# Sheet_1_2023-04-12.net
KiCad netlist of a schematic drawn in Altium Designer
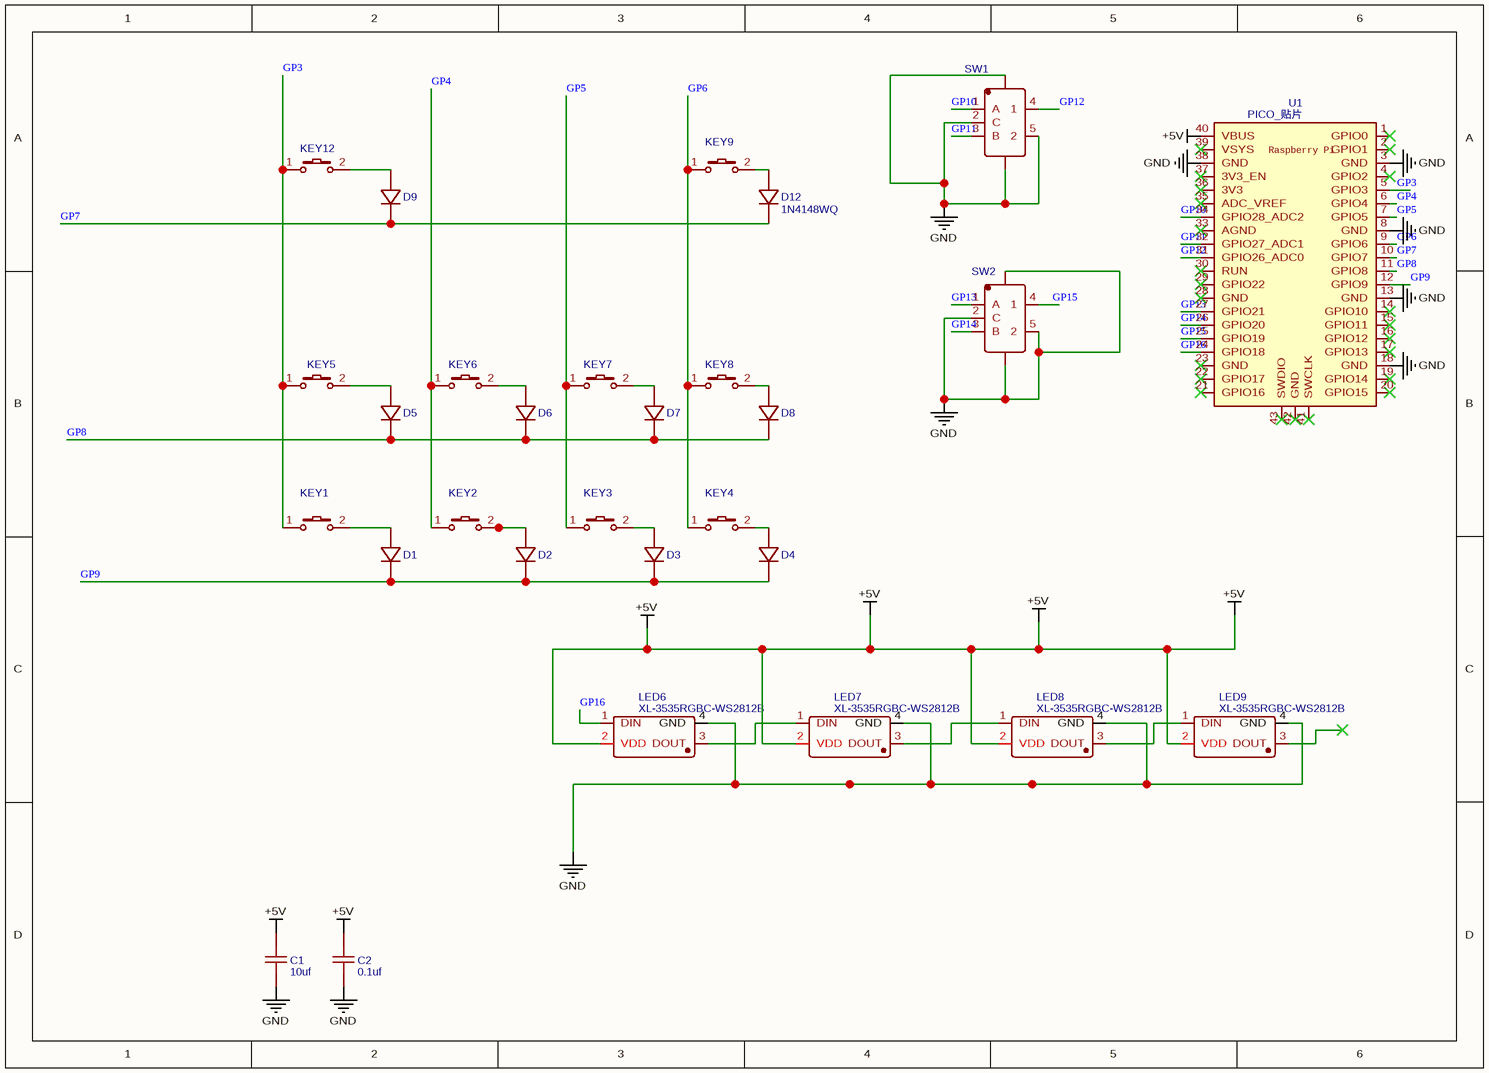
[diagram p0: Sheet_1_2023-04-12.schdoc]

(export (version "E")
  (design (tool "Eeschema 10.0.6"))
  (components
    (comp (ref "C1")
      (value "10uf")
      (fields (field (name "CONTRIBUTOR") "LCEDA_Lib"))
      (libsource (lib "altium-import") (part "root_1_10uf_"))
    )
    (comp (ref "C2")
      (value "0.1uf")
      (fields (field (name "CONTRIBUTOR") "LCEDA_Lib"))
      (libsource (lib "altium-import") (part "root_1_0.1uf_"))
    )
    (comp (ref "D1")
      (value "1N4148WQ")
      (fields (field (name "BOM_SUPPLIER PART") "C2942441") (field (name "CONTRIBUTOR") "lcsc"))
      (libsource (lib "altium-import") (part "root_1_1N4148WQ_"))
    )
    (comp (ref "D2")
      (value "1N4148WQ")
      (fields (field (name "BOM_SUPPLIER PART") "C2942441") (field (name "CONTRIBUTOR") "lcsc"))
      (libsource (lib "altium-import") (part "root_1_1N4148WQ_"))
    )
    (comp (ref "D3")
      (value "1N4148WQ")
      (fields (field (name "BOM_SUPPLIER PART") "C2942441") (field (name "CONTRIBUTOR") "lcsc"))
      (libsource (lib "altium-import") (part "root_1_1N4148WQ_"))
    )
    (comp (ref "D4")
      (value "1N4148WQ")
      (fields (field (name "BOM_SUPPLIER PART") "C2942441") (field (name "CONTRIBUTOR") "lcsc"))
      (libsource (lib "altium-import") (part "root_1_1N4148WQ_"))
    )
    (comp (ref "D5")
      (value "1N4148WQ")
      (fields (field (name "BOM_SUPPLIER PART") "C2942441") (field (name "CONTRIBUTOR") "lcsc"))
      (libsource (lib "altium-import") (part "root_1_1N4148WQ_"))
    )
    (comp (ref "D6")
      (value "1N4148WQ")
      (fields (field (name "BOM_SUPPLIER PART") "C2942441") (field (name "CONTRIBUTOR") "lcsc"))
      (libsource (lib "altium-import") (part "root_1_1N4148WQ_"))
    )
    (comp (ref "D7")
      (value "1N4148WQ")
      (fields (field (name "BOM_SUPPLIER PART") "C2942441") (field (name "CONTRIBUTOR") "lcsc"))
      (libsource (lib "altium-import") (part "root_1_1N4148WQ_"))
    )
    (comp (ref "D8")
      (value "1N4148WQ")
      (fields (field (name "BOM_SUPPLIER PART") "C2942441") (field (name "CONTRIBUTOR") "lcsc"))
      (libsource (lib "altium-import") (part "root_1_1N4148WQ_"))
    )
    (comp (ref "D9")
      (value "1N4148WQ")
      (fields (field (name "BOM_SUPPLIER PART") "C2942441") (field (name "CONTRIBUTOR") "lcsc"))
      (libsource (lib "altium-import") (part "root_1_1N4148WQ_"))
    )
    (comp (ref "D12")
      (value "1N4148WQ")
      (fields (field (name "BOM_SUPPLIER PART") "C2942441") (field (name "CONTRIBUTOR") "lcsc"))
      (libsource (lib "altium-import") (part "root_1_1N4148WQ_"))
    )
    (comp (ref "KEY1")
      (value "K2-3.6×6.1_SMD")
      (fields
        (field (name "BOM_SUPPLIER PART") "C118141")
        (field (name "BOM_MANUFACTURER PART") "K2-1107ST-A4SW-06")
        (field (name "CONTRIBUTOR") "LCEDA_Lib")
      )
      (libsource (lib "altium-import") (part "root_0_K2-3.6×6.1_SMD_"))
    )
    (comp (ref "KEY2")
      (value "K2-3.6×6.1_SMD")
      (fields
        (field (name "BOM_SUPPLIER PART") "C118141")
        (field (name "BOM_MANUFACTURER PART") "K2-1107ST-A4SW-06")
        (field (name "CONTRIBUTOR") "LCEDA_Lib")
      )
      (libsource (lib "altium-import") (part "root_0_K2-3.6×6.1_SMD_"))
    )
    (comp (ref "KEY3")
      (value "K2-3.6×6.1_SMD")
      (fields
        (field (name "BOM_SUPPLIER PART") "C118141")
        (field (name "BOM_MANUFACTURER PART") "K2-1107ST-A4SW-06")
        (field (name "CONTRIBUTOR") "LCEDA_Lib")
      )
      (libsource (lib "altium-import") (part "root_0_K2-3.6×6.1_SMD_"))
    )
    (comp (ref "KEY4")
      (value "K2-3.6×6.1_SMD")
      (fields
        (field (name "BOM_SUPPLIER PART") "C118141")
        (field (name "BOM_MANUFACTURER PART") "K2-1107ST-A4SW-06")
        (field (name "CONTRIBUTOR") "LCEDA_Lib")
      )
      (libsource (lib "altium-import") (part "root_0_K2-3.6×6.1_SMD_"))
    )
    (comp (ref "KEY5")
      (value "K2-3.6×6.1_SMD")
      (fields
        (field (name "BOM_SUPPLIER PART") "C118141")
        (field (name "BOM_MANUFACTURER PART") "K2-1107ST-A4SW-06")
        (field (name "CONTRIBUTOR") "LCEDA_Lib")
      )
      (libsource (lib "altium-import") (part "root_0_K2-3.6×6.1_SMD_"))
    )
    (comp (ref "KEY6")
      (value "K2-3.6×6.1_SMD")
      (fields
        (field (name "BOM_SUPPLIER PART") "C118141")
        (field (name "BOM_MANUFACTURER PART") "K2-1107ST-A4SW-06")
        (field (name "CONTRIBUTOR") "LCEDA_Lib")
      )
      (libsource (lib "altium-import") (part "root_0_K2-3.6×6.1_SMD_"))
    )
    (comp (ref "KEY7")
      (value "K2-3.6×6.1_SMD")
      (fields
        (field (name "BOM_SUPPLIER PART") "C118141")
        (field (name "BOM_MANUFACTURER PART") "K2-1107ST-A4SW-06")
        (field (name "CONTRIBUTOR") "LCEDA_Lib")
      )
      (libsource (lib "altium-import") (part "root_0_K2-3.6×6.1_SMD_"))
    )
    (comp (ref "KEY8")
      (value "K2-3.6×6.1_SMD")
      (fields
        (field (name "BOM_SUPPLIER PART") "C118141")
        (field (name "BOM_MANUFACTURER PART") "K2-1107ST-A4SW-06")
        (field (name "CONTRIBUTOR") "LCEDA_Lib")
      )
      (libsource (lib "altium-import") (part "root_0_K2-3.6×6.1_SMD_"))
    )
    (comp (ref "KEY9")
      (value "K2-3.6×6.1_SMD")
      (fields
        (field (name "BOM_SUPPLIER PART") "C118141")
        (field (name "BOM_MANUFACTURER PART") "K2-1107ST-A4SW-06")
        (field (name "CONTRIBUTOR") "LCEDA_Lib")
      )
      (libsource (lib "altium-import") (part "root_0_K2-3.6×6.1_SMD_"))
    )
    (comp (ref "KEY12")
      (value "K2-3.6×6.1_SMD")
      (fields
        (field (name "BOM_SUPPLIER PART") "C118141")
        (field (name "BOM_MANUFACTURER PART") "K2-1107ST-A4SW-06")
        (field (name "CONTRIBUTOR") "LCEDA_Lib")
      )
      (libsource (lib "altium-import") (part "root_0_K2-3.6×6.1_SMD_"))
    )
    (comp (ref "LED6")
      (value "XL-3535RGBC-WS2812B")
      (fields (field (name "BOM_SUPPLIER PART") "C2843786") (field (name "CONTRIBUTOR") "LCSC"))
      (libsource (lib "altium-import") (part "root_2_XL-3535RGBC-WS2812B_"))
    )
    (comp (ref "LED7")
      (value "XL-3535RGBC-WS2812B")
      (fields (field (name "BOM_SUPPLIER PART") "C2843786") (field (name "CONTRIBUTOR") "LCSC"))
      (libsource (lib "altium-import") (part "root_2_XL-3535RGBC-WS2812B_"))
    )
    (comp (ref "LED8")
      (value "XL-3535RGBC-WS2812B")
      (fields (field (name "BOM_SUPPLIER PART") "C2843786") (field (name "CONTRIBUTOR") "LCSC"))
      (libsource (lib "altium-import") (part "root_2_XL-3535RGBC-WS2812B_"))
    )
    (comp (ref "LED9")
      (value "XL-3535RGBC-WS2812B")
      (fields (field (name "BOM_SUPPLIER PART") "C2843786") (field (name "CONTRIBUTOR") "LCSC"))
      (libsource (lib "altium-import") (part "root_2_XL-3535RGBC-WS2812B_"))
    )
    (comp (ref "SW1")
      (value "PEC11R-4215F-S0024")
      (fields (field (name "BOM_SUPPLIER PART") "C143790") (field (name "CONTRIBUTOR") "LCSC"))
      (libsource (lib "altium-import") (part "root_0_PEC11R-4215F-S0024_"))
    )
    (comp (ref "SW2")
      (value "PEC11R-4215F-S0024")
      (fields (field (name "BOM_SUPPLIER PART") "C143790") (field (name "CONTRIBUTOR") "LCSC"))
      (libsource (lib "altium-import") (part "root_0_PEC11R-4215F-S0024_"))
    )
    (comp (ref "U1")
      (value "PICO_贴片")
      (fields (field (name "CONTRIBUTOR") "NicolassZuo"))
      (libsource (lib "altium-import") (part "root_0_PICO_贴片_"))
    )
  )
  (nets
    (net (code "1") (name "+5V") (class "Default")
      (node (ref "C1") (pin "2") (pinfunction "2_2") (pintype "passive"))
      (node (ref "C2") (pin "2") (pinfunction "2_2") (pintype "passive"))
      (node (ref "LED6") (pin "2") (pinfunction "VDD_2") (pintype "passive"))
      (node (ref "LED7") (pin "2") (pinfunction "VDD_2") (pintype "passive"))
      (node (ref "LED8") (pin "2") (pinfunction "VDD_2") (pintype "passive"))
      (node (ref "LED9") (pin "2") (pinfunction "VDD_2") (pintype "passive"))
      (node (ref "U1") (pin "40") (pinfunction "VBUS_40") (pintype "passive"))
    )
    (net (code "2") (name "/GP3") (class "Default")
      (node (ref "KEY1") (pin "1") (pinfunction "1_1") (pintype "passive"))
      (node (ref "KEY12") (pin "1") (pinfunction "1_1") (pintype "passive"))
      (node (ref "KEY5") (pin "1") (pinfunction "1_1") (pintype "passive"))
      (node (ref "U1") (pin "5") (pinfunction "GPIO3_5") (pintype "passive"))
    )
    (net (code "3") (name "/GP4") (class "Default")
      (node (ref "KEY2") (pin "1") (pinfunction "1_1") (pintype "passive"))
      (node (ref "KEY6") (pin "1") (pinfunction "1_1") (pintype "passive"))
      (node (ref "U1") (pin "6") (pinfunction "GPIO4_6") (pintype "passive"))
    )
    (net (code "4") (name "/GP5") (class "Default")
      (node (ref "KEY3") (pin "1") (pinfunction "1_1") (pintype "passive"))
      (node (ref "KEY7") (pin "1") (pinfunction "1_1") (pintype "passive"))
      (node (ref "U1") (pin "7") (pinfunction "GPIO5_7") (pintype "passive"))
    )
    (net (code "5") (name "/GP6") (class "Default")
      (node (ref "KEY4") (pin "1") (pinfunction "1_1") (pintype "passive"))
      (node (ref "KEY8") (pin "1") (pinfunction "1_1") (pintype "passive"))
      (node (ref "KEY9") (pin "1") (pinfunction "1_1") (pintype "passive"))
      (node (ref "U1") (pin "9") (pinfunction "GPIO6_9") (pintype "passive"))
    )
    (net (code "6") (name "/GP7") (class "Default")
      (node (ref "D12") (pin "1") (pinfunction "K_1") (pintype "passive"))
      (node (ref "D9") (pin "1") (pinfunction "K_1") (pintype "passive"))
      (node (ref "U1") (pin "10") (pinfunction "GPIO7_10") (pintype "passive"))
    )
    (net (code "7") (name "/GP8") (class "Default")
      (node (ref "D5") (pin "1") (pinfunction "K_1") (pintype "passive"))
      (node (ref "D6") (pin "1") (pinfunction "K_1") (pintype "passive"))
      (node (ref "D7") (pin "1") (pinfunction "K_1") (pintype "passive"))
      (node (ref "D8") (pin "1") (pinfunction "K_1") (pintype "passive"))
      (node (ref "U1") (pin "11") (pinfunction "GPIO8_11") (pintype "passive"))
    )
    (net (code "8") (name "/GP9") (class "Default")
      (node (ref "D1") (pin "1") (pinfunction "K_1") (pintype "passive"))
      (node (ref "D2") (pin "1") (pinfunction "K_1") (pintype "passive"))
      (node (ref "D3") (pin "1") (pinfunction "K_1") (pintype "passive"))
      (node (ref "D4") (pin "1") (pinfunction "K_1") (pintype "passive"))
      (node (ref "U1") (pin "12") (pinfunction "GPIO9_12") (pintype "passive"))
    )
    (net (code "9") (name "/GP10") (class "Default")
      (node (ref "SW1") (pin "1") (pinfunction "A_1") (pintype "passive"))
      (node (ref "U1") (pin "34") (pinfunction "GPIO28_ADC2_34") (pintype "passive"))
    )
    (net (code "10") (name "/GP11") (class "Default")
      (node (ref "SW1") (pin "3") (pinfunction "B_3") (pintype "passive"))
      (node (ref "U1") (pin "32") (pinfunction "GPIO27_ADC1_32") (pintype "passive"))
    )
    (net (code "11") (name "/GP12") (class "Default")
      (node (ref "SW1") (pin "4") (pinfunction "1_4") (pintype "passive"))
      (node (ref "U1") (pin "31") (pinfunction "GPIO26_ADC0_31") (pintype "passive"))
    )
    (net (code "12") (name "/GP13") (class "Default")
      (node (ref "SW2") (pin "1") (pinfunction "A_1") (pintype "passive"))
      (node (ref "U1") (pin "27") (pinfunction "GPIO21_27") (pintype "passive"))
    )
    (net (code "13") (name "/GP14") (class "Default")
      (node (ref "SW2") (pin "3") (pinfunction "B_3") (pintype "passive"))
      (node (ref "U1") (pin "26") (pinfunction "GPIO20_26") (pintype "passive"))
    )
    (net (code "14") (name "/GP15") (class "Default")
      (node (ref "SW2") (pin "4") (pinfunction "1_4") (pintype "passive"))
      (node (ref "U1") (pin "25") (pinfunction "GPIO19_25") (pintype "passive"))
    )
    (net (code "15") (name "/GP16") (class "Default")
      (node (ref "LED6") (pin "1") (pinfunction "DIN_1") (pintype "passive"))
      (node (ref "U1") (pin "24") (pinfunction "GPIO18_24") (pintype "passive"))
    )
    (net (code "16") (name "GND") (class "Default")
      (node (ref "C1") (pin "1") (pinfunction "1_1") (pintype "passive"))
      (node (ref "C2") (pin "1") (pinfunction "1_1") (pintype "passive"))
      (node (ref "LED6") (pin "4") (pinfunction "GND_4") (pintype "passive"))
      (node (ref "LED7") (pin "4") (pinfunction "GND_4") (pintype "passive"))
      (node (ref "LED8") (pin "4") (pinfunction "GND_4") (pintype "passive"))
      (node (ref "LED9") (pin "4") (pinfunction "GND_4") (pintype "passive"))
      (node (ref "SW1") (pin "2") (pinfunction "C_2") (pintype "passive"))
      (node (ref "SW1") (pin "5") (pinfunction "2_5") (pintype "passive"))
      (node (ref "SW1") (pin "7") (pinfunction "7_7") (pintype "passive"))
      (node (ref "SW1") (pin "8") (pinfunction "8_8") (pintype "passive"))
      (node (ref "SW2") (pin "2") (pinfunction "C_2") (pintype "passive"))
      (node (ref "SW2") (pin "5") (pinfunction "2_5") (pintype "passive"))
      (node (ref "SW2") (pin "7") (pinfunction "7_7") (pintype "passive"))
      (node (ref "SW2") (pin "8") (pinfunction "8_8") (pintype "passive"))
      (node (ref "U1") (pin "13") (pinfunction "GND_13") (pintype "passive"))
      (node (ref "U1") (pin "18") (pinfunction "GND_18") (pintype "passive"))
      (node (ref "U1") (pin "3") (pinfunction "GND_3") (pintype "passive"))
      (node (ref "U1") (pin "38") (pinfunction "GND_38") (pintype "passive"))
      (node (ref "U1") (pin "8") (pinfunction "GND_8") (pintype "passive"))
    )
    (net (code "17") (name "Net-(D1-A)") (class "Default")
      (node (ref "D1") (pin "2") (pinfunction "A_2") (pintype "passive"))
      (node (ref "KEY1") (pin "2") (pinfunction "2_2") (pintype "passive"))
    )
    (net (code "18") (name "Net-(D2-A)") (class "Default")
      (node (ref "D2") (pin "2") (pinfunction "A_2") (pintype "passive"))
      (node (ref "KEY2") (pin "2") (pinfunction "2_2") (pintype "passive"))
    )
    (net (code "19") (name "Net-(D3-A)") (class "Default")
      (node (ref "D3") (pin "2") (pinfunction "A_2") (pintype "passive"))
      (node (ref "KEY3") (pin "2") (pinfunction "2_2") (pintype "passive"))
    )
    (net (code "20") (name "Net-(D4-A)") (class "Default")
      (node (ref "D4") (pin "2") (pinfunction "A_2") (pintype "passive"))
      (node (ref "KEY4") (pin "2") (pinfunction "2_2") (pintype "passive"))
    )
    (net (code "21") (name "Net-(D5-A)") (class "Default")
      (node (ref "D5") (pin "2") (pinfunction "A_2") (pintype "passive"))
      (node (ref "KEY5") (pin "2") (pinfunction "2_2") (pintype "passive"))
    )
    (net (code "22") (name "Net-(D6-A)") (class "Default")
      (node (ref "D6") (pin "2") (pinfunction "A_2") (pintype "passive"))
      (node (ref "KEY6") (pin "2") (pinfunction "2_2") (pintype "passive"))
    )
    (net (code "23") (name "Net-(D7-A)") (class "Default")
      (node (ref "D7") (pin "2") (pinfunction "A_2") (pintype "passive"))
      (node (ref "KEY7") (pin "2") (pinfunction "2_2") (pintype "passive"))
    )
    (net (code "24") (name "Net-(D8-A)") (class "Default")
      (node (ref "D8") (pin "2") (pinfunction "A_2") (pintype "passive"))
      (node (ref "KEY8") (pin "2") (pinfunction "2_2") (pintype "passive"))
    )
    (net (code "25") (name "Net-(D9-A)") (class "Default")
      (node (ref "D9") (pin "2") (pinfunction "A_2") (pintype "passive"))
      (node (ref "KEY12") (pin "2") (pinfunction "2_2") (pintype "passive"))
    )
    (net (code "26") (name "Net-(D12-A)") (class "Default")
      (node (ref "D12") (pin "2") (pinfunction "A_2") (pintype "passive"))
      (node (ref "KEY9") (pin "2") (pinfunction "2_2") (pintype "passive"))
    )
    (net (code "27") (name "Net-(LED6-DOUT)") (class "Default")
      (node (ref "LED6") (pin "3") (pinfunction "DOUT_3") (pintype "passive"))
      (node (ref "LED7") (pin "1") (pinfunction "DIN_1") (pintype "passive"))
    )
    (net (code "28") (name "Net-(LED7-DOUT)") (class "Default")
      (node (ref "LED7") (pin "3") (pinfunction "DOUT_3") (pintype "passive"))
      (node (ref "LED8") (pin "1") (pinfunction "DIN_1") (pintype "passive"))
    )
    (net (code "29") (name "Net-(LED8-DOUT)") (class "Default")
      (node (ref "LED8") (pin "3") (pinfunction "DOUT_3") (pintype "passive"))
      (node (ref "LED9") (pin "1") (pinfunction "DIN_1") (pintype "passive"))
    )
    (net (code "30") (name "unconnected-(LED9-DOUT-Pad3)") (class "Default")
      (node (ref "LED9") (pin "3") (pinfunction "DOUT_3") (pintype "passive+no_connect"))
    )
    (net (code "31") (name "unconnected-(U1-3V3-Pad36)") (class "Default")
      (node (ref "U1") (pin "36") (pinfunction "3V3_36") (pintype "passive+no_connect"))
    )
    (net (code "32") (name "unconnected-(U1-3V3_EN-Pad37)") (class "Default")
      (node (ref "U1") (pin "37") (pinfunction "3V3_EN_37") (pintype "passive+no_connect"))
    )
    (net (code "33") (name "unconnected-(U1-ADC_VREF-Pad35)") (class "Default")
      (node (ref "U1") (pin "35") (pinfunction "ADC_VREF_35") (pintype "passive+no_connect"))
    )
    (net (code "34") (name "unconnected-(U1-AGND-Pad33)") (class "Default")
      (node (ref "U1") (pin "33") (pinfunction "AGND_33") (pintype "passive+no_connect"))
    )
    (net (code "35") (name "unconnected-(U1-GND-Pad23)") (class "Default")
      (node (ref "U1") (pin "23") (pinfunction "GND_23") (pintype "passive+no_connect"))
    )
    (net (code "36") (name "unconnected-(U1-GND-Pad28)") (class "Default")
      (node (ref "U1") (pin "28") (pinfunction "GND_28") (pintype "passive+no_connect"))
    )
    (net (code "37") (name "unconnected-(U1-GND-Pad42)") (class "Default")
      (node (ref "U1") (pin "42") (pinfunction "GND_42") (pintype "passive+no_connect"))
    )
    (net (code "38") (name "unconnected-(U1-GPIO0-Pad1)") (class "Default")
      (node (ref "U1") (pin "1") (pinfunction "GPIO0_1") (pintype "passive+no_connect"))
    )
    (net (code "39") (name "unconnected-(U1-GPIO1-Pad2)") (class "Default")
      (node (ref "U1") (pin "2") (pinfunction "GPIO1_2") (pintype "passive+no_connect"))
    )
    (net (code "40") (name "unconnected-(U1-GPIO2-Pad4)") (class "Default")
      (node (ref "U1") (pin "4") (pinfunction "GPIO2_4") (pintype "passive+no_connect"))
    )
    (net (code "41") (name "unconnected-(U1-GPIO10-Pad14)") (class "Default")
      (node (ref "U1") (pin "14") (pinfunction "GPIO10_14") (pintype "passive+no_connect"))
    )
    (net (code "42") (name "unconnected-(U1-GPIO11-Pad15)") (class "Default")
      (node (ref "U1") (pin "15") (pinfunction "GPIO11_15") (pintype "passive+no_connect"))
    )
    (net (code "43") (name "unconnected-(U1-GPIO12-Pad16)") (class "Default")
      (node (ref "U1") (pin "16") (pinfunction "GPIO12_16") (pintype "passive+no_connect"))
    )
    (net (code "44") (name "unconnected-(U1-GPIO13-Pad17)") (class "Default")
      (node (ref "U1") (pin "17") (pinfunction "GPIO13_17") (pintype "passive+no_connect"))
    )
    (net (code "45") (name "unconnected-(U1-GPIO14-Pad19)") (class "Default")
      (node (ref "U1") (pin "19") (pinfunction "GPIO14_19") (pintype "passive+no_connect"))
    )
    (net (code "46") (name "unconnected-(U1-GPIO15-Pad20)") (class "Default")
      (node (ref "U1") (pin "20") (pinfunction "GPIO15_20") (pintype "passive+no_connect"))
    )
    (net (code "47") (name "unconnected-(U1-GPIO16-Pad21)") (class "Default")
      (node (ref "U1") (pin "21") (pinfunction "GPIO16_21") (pintype "passive+no_connect"))
    )
    (net (code "48") (name "unconnected-(U1-GPIO17-Pad22)") (class "Default")
      (node (ref "U1") (pin "22") (pinfunction "GPIO17_22") (pintype "passive+no_connect"))
    )
    (net (code "49") (name "unconnected-(U1-GPIO22-Pad29)") (class "Default")
      (node (ref "U1") (pin "29") (pinfunction "GPIO22_29") (pintype "passive+no_connect"))
    )
    (net (code "50") (name "unconnected-(U1-RUN-Pad30)") (class "Default")
      (node (ref "U1") (pin "30") (pinfunction "RUN_30") (pintype "passive+no_connect"))
    )
    (net (code "51") (name "unconnected-(U1-SWCLK-Pad41)") (class "Default")
      (node (ref "U1") (pin "41") (pinfunction "SWCLK_41") (pintype "passive+no_connect"))
    )
    (net (code "52") (name "unconnected-(U1-SWDIO-Pad43)") (class "Default")
      (node (ref "U1") (pin "43") (pinfunction "SWDIO_43") (pintype "passive+no_connect"))
    )
    (net (code "53") (name "unconnected-(U1-VSYS-Pad39)") (class "Default")
      (node (ref "U1") (pin "39") (pinfunction "VSYS_39") (pintype "passive+no_connect"))
    )
  )
)
